# 85_SOP8_v2.net
KiCad netlist of a schematic drawn in EAGLE
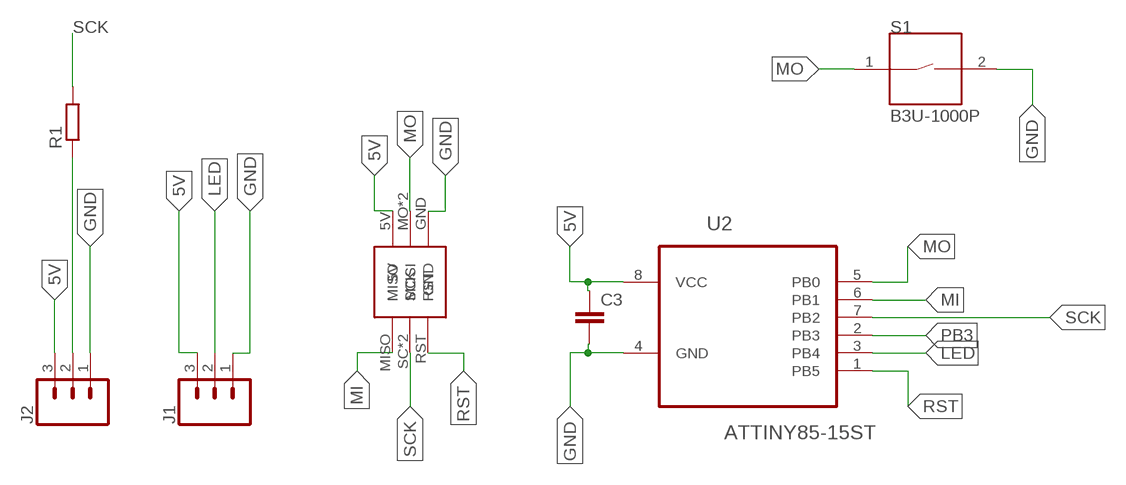
[diagram p0: schematic, sheet 1]

(export (version "E")
  (design (tool "Eeschema 10.0.6"))
  (components
    (comp (ref "C3")
      (value "C-EUC0603")
      (footprint "eagle-import:C0603")
      (libsource (lib "eagle-import") (part "C-EUC0603"))
    )
    (comp (ref "J1")
      (value "CONN_031X03_NO_SILK")
      (footprint "eagle-import:1X03_NO_SILK")
      (libsource (lib "eagle-import") (part "CONN_031X03_NO_SILK"))
    )
    (comp (ref "J2")
      (value "CONN_031X03_NO_SILK")
      (footprint "eagle-import:1X03_NO_SILK")
      (libsource (lib "eagle-import") (part "CONN_031X03_NO_SILK"))
    )
    (comp (ref "R1")
      (value "R-EU_R0603")
      (footprint "eagle-import:R0603")
      (libsource (lib "eagle-import") (part "R-EU_R0603"))
    )
    (comp (ref "S1")
      (value "B3U-1000P")
      (footprint "eagle-import:SW_B3U-1000P")
      (fields (field (name "MF") "Omron"))
      (libsource (lib "eagle-import") (part "B3U-1000P"))
    )
    (comp (ref "U$1")
      (value "ISCP_PORTPOGONEW")
      (footprint "eagle-import:ISCP_PADS_2ROW2HNEW")
      (libsource (lib "eagle-import") (part "ISCP_PORTPOGONEW"))
    )
    (comp (ref "U2")
      (value "ATTINY85-15ST")
      (footprint "eagle-import:SOIC127P798X216-8N")
      (fields (field (name "MF") "Microchip"))
      (libsource (lib "eagle-import") (part "ATTINY85-15ST"))
    )
  )
  (nets
    (net (code "1") (name "5V") (class "Default")
      (node (ref "C3") (pin "1") (pinfunction "1_1") (pintype "passive"))
      (node (ref "J1") (pin "3") (pinfunction "3_3") (pintype "passive"))
      (node (ref "J2") (pin "3") (pinfunction "3_3") (pintype "passive"))
      (node (ref "U$1") (pin "5V") (pinfunction "5V_5V") (pintype "bidirectional"))
      (node (ref "U2") (pin "8") (pinfunction "VCC_8") (pintype "power_in"))
    )
    (net (code "2") (name "GND") (class "Default")
      (node (ref "C3") (pin "2") (pinfunction "2_2") (pintype "passive"))
      (node (ref "J1") (pin "1") (pinfunction "1_1") (pintype "passive"))
      (node (ref "J2") (pin "1") (pinfunction "1_1") (pintype "passive"))
      (node (ref "S1") (pin "2") (pinfunction "2_2") (pintype "passive"))
      (node (ref "U$1") (pin "GND") (pinfunction "GND_GND") (pintype "bidirectional"))
      (node (ref "U2") (pin "4") (pinfunction "GND_4") (pintype "passive"))
    )
    (net (code "3") (name "LED") (class "Default")
      (node (ref "J1") (pin "2") (pinfunction "2_2") (pintype "passive"))
      (node (ref "U2") (pin "3") (pinfunction "PB4_3") (pintype "bidirectional"))
    )
    (net (code "4") (name "MI") (class "Default")
      (node (ref "U$1") (pin "MISO") (pinfunction "MISO_MISO") (pintype "bidirectional"))
      (node (ref "U2") (pin "6") (pinfunction "PB1_6") (pintype "bidirectional"))
    )
    (net (code "5") (name "MO") (class "Default")
      (node (ref "S1") (pin "1") (pinfunction "1_1") (pintype "passive"))
      (node (ref "U$1") (pin "MO") (pinfunction "MOSI_MO") (pintype "bidirectional"))
      (node (ref "U$1") (pin "MOSI") (pinfunction "MOSI_MOSI") (pintype "bidirectional"))
      (node (ref "U2") (pin "5") (pinfunction "PB0_5") (pintype "bidirectional"))
    )
    (net (code "6") (name "Net-(J2-Pad2)") (class "Default")
      (node (ref "J2") (pin "2") (pinfunction "2_2") (pintype "passive"))
      (node (ref "R1") (pin "1") (pinfunction "1_1") (pintype "passive"))
    )
    (net (code "7") (name "PB3") (class "Default")
      (node (ref "U2") (pin "2") (pinfunction "PB3_2") (pintype "bidirectional"))
    )
    (net (code "8") (name "RST") (class "Default")
      (node (ref "U$1") (pin "RST") (pinfunction "RST_RST") (pintype "bidirectional"))
      (node (ref "U2") (pin "1") (pinfunction "PB5_1") (pintype "bidirectional"))
    )
    (net (code "9") (name "SCK") (class "Default")
      (node (ref "R1") (pin "2") (pinfunction "2_2") (pintype "passive"))
      (node (ref "U$1") (pin "SC") (pinfunction "SCK_SC") (pintype "bidirectional"))
      (node (ref "U$1") (pin "SCK") (pinfunction "SCK_SCK") (pintype "bidirectional"))
      (node (ref "U2") (pin "7") (pinfunction "PB2_7") (pintype "bidirectional"))
    )
  )
)
